# ProDoc_P1_2025-11-01.net
KiCad netlist of a schematic drawn in EasyEDA Pro
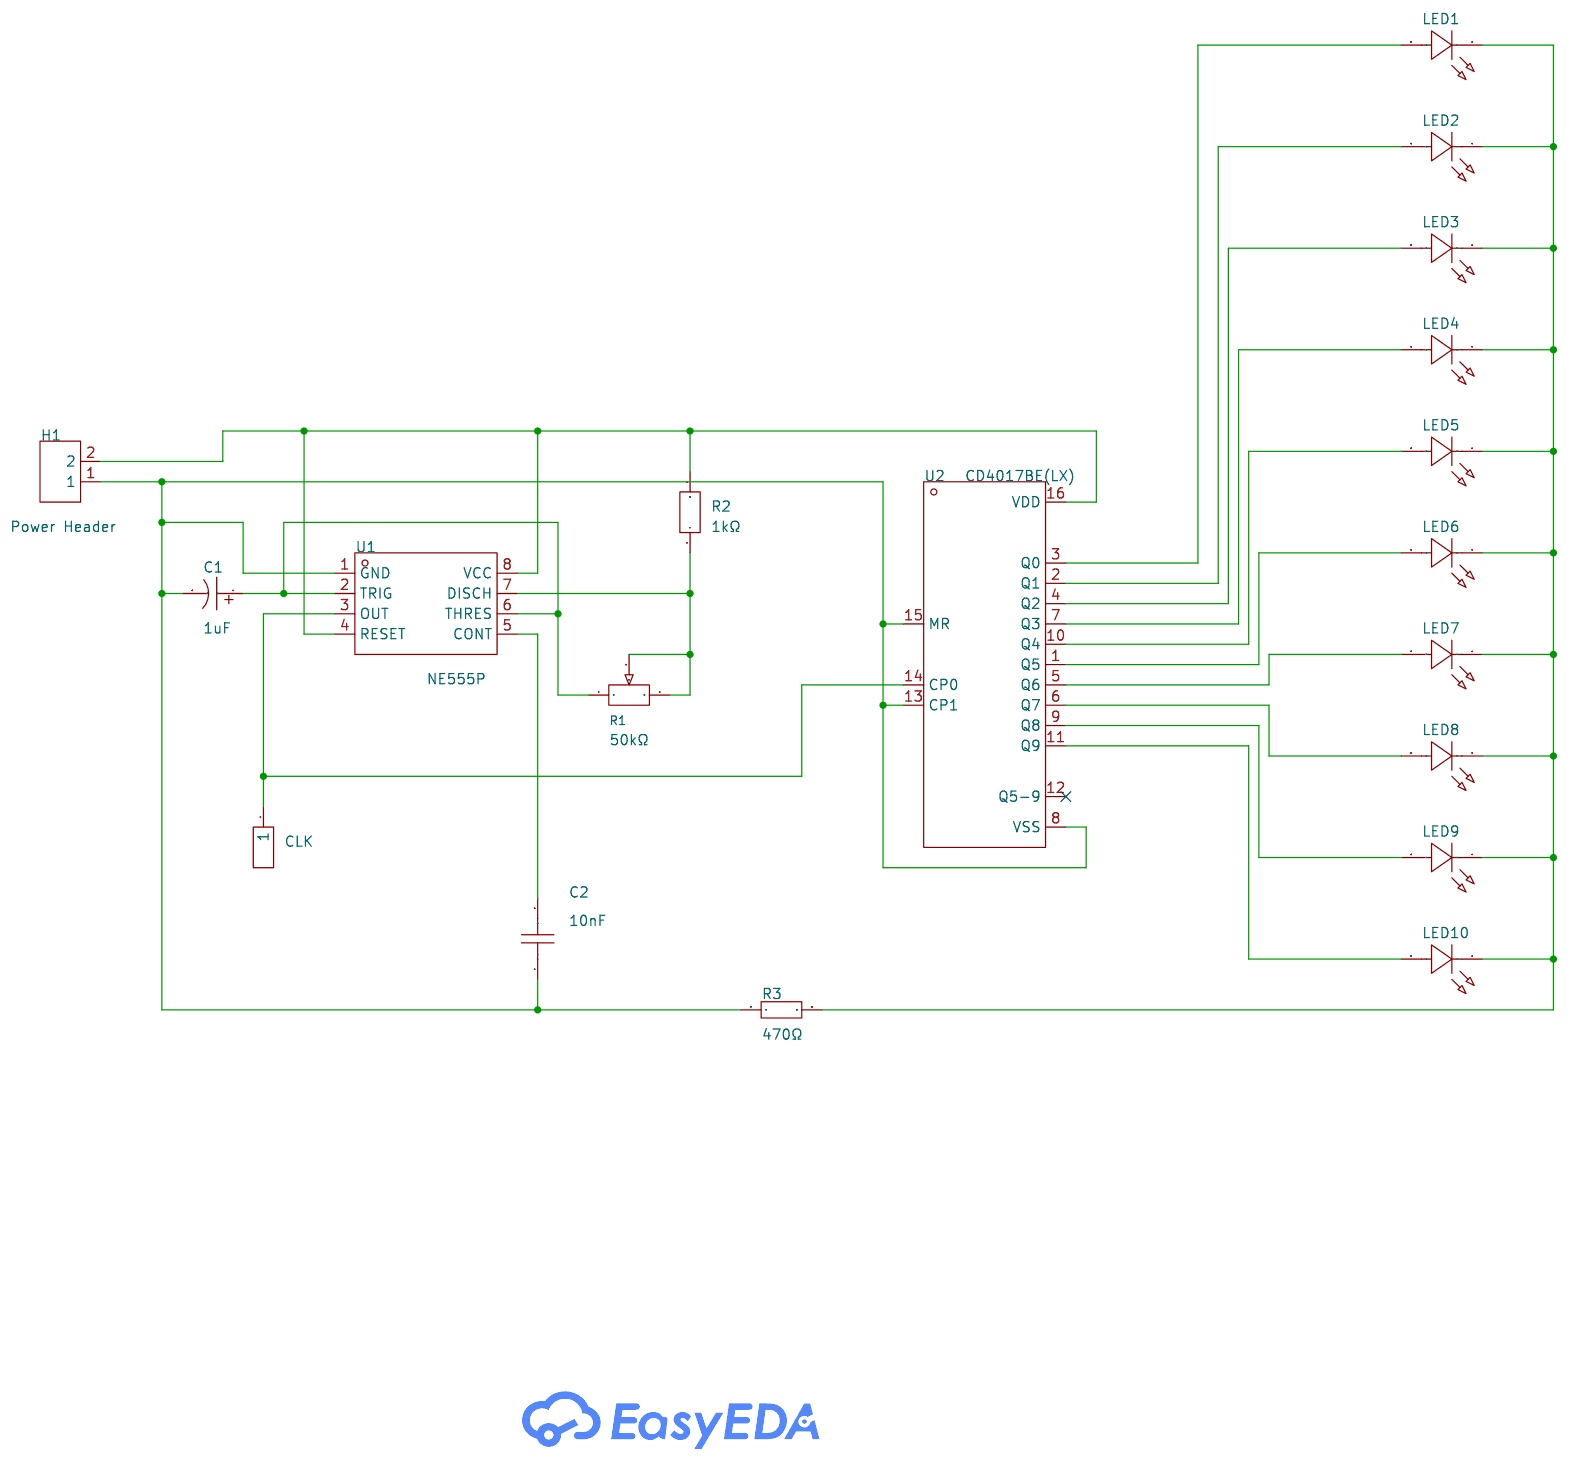
[diagram p0: schematic sheet]

(export (version "E")
  (design (tool "Eeschema 10.0.6"))
  (components
    (comp (ref "C1")
      (value "1uF")
      (footprint "easyedapro:CAP-TH_BD5.0-P2.00-D0.8-FD")
      (fields (field (name "Manufacturer Part") "KF010M050C110A") (field (name "Manufacturer") "CapXon(丰宾)"))
      (libsource (lib "easyedapro") (part "KF010M050C110A"))
    )
    (comp (ref "C2")
      (value "10nF")
      (footprint "easyedapro:CAP-TH_L8.0-W4.0-P5.00-D1.2")
      (fields (field (name "Manufacturer Part") "N09F1B103MN0B0S0N0") (field (name "Manufacturer") "STE(松田)"))
      (libsource (lib "easyedapro") (part "N09F1B103MN0B0S0N0"))
    )
    (comp (ref "CLK")
      (value "2.54-1*1P针")
      (footprint "easyedapro:HDR-TH_1P-P2.54-V-M")
      (fields (field (name "Manufacturer") "BOOMELE(博穆精密)"))
      (libsource (lib "easyedapro") (part "Header-Male-2.54_1x1"))
    )
    (comp (ref "H1")
      (value "Power Header")
      (footprint "easyedapro:HDR-TH_2P-P2.54-V-M")
      (fields (field (name "Manufacturer") "XFCN(兴飞)"))
      (libsource (lib "easyedapro") (part "PZ254V-11-02P"))
    )
    (comp (ref "LED1")
      (value "XL-502UWC")
      (footprint "easyedapro:LED-TH_BD5.9-P2.54-RD_WHITE")
      (fields (field (name "Manufacturer") "XINGLIGHT(成兴光)"))
      (libsource (lib "easyedapro") (part "XL-502UWC"))
    )
    (comp (ref "LED2")
      (value "XL-502UWC")
      (footprint "easyedapro:LED-TH_BD5.9-P2.54-RD_WHITE")
      (fields (field (name "Manufacturer") "XINGLIGHT(成兴光)"))
      (libsource (lib "easyedapro") (part "XL-502UWC"))
    )
    (comp (ref "LED3")
      (value "XL-502UWC")
      (footprint "easyedapro:LED-TH_BD5.9-P2.54-RD_WHITE")
      (fields (field (name "Manufacturer") "XINGLIGHT(成兴光)"))
      (libsource (lib "easyedapro") (part "XL-502UWC"))
    )
    (comp (ref "LED4")
      (value "XL-502UWC")
      (footprint "easyedapro:LED-TH_BD5.9-P2.54-RD_WHITE")
      (fields (field (name "Manufacturer") "XINGLIGHT(成兴光)"))
      (libsource (lib "easyedapro") (part "XL-502UWC"))
    )
    (comp (ref "LED5")
      (value "XL-502UWC")
      (footprint "easyedapro:LED-TH_BD5.9-P2.54-RD_WHITE")
      (fields (field (name "Manufacturer") "XINGLIGHT(成兴光)"))
      (libsource (lib "easyedapro") (part "XL-502UWC"))
    )
    (comp (ref "LED6")
      (value "XL-502UWC")
      (footprint "easyedapro:LED-TH_BD5.9-P2.54-RD_WHITE")
      (fields (field (name "Manufacturer") "XINGLIGHT(成兴光)"))
      (libsource (lib "easyedapro") (part "XL-502UWC"))
    )
    (comp (ref "LED7")
      (value "XL-502UWC")
      (footprint "easyedapro:LED-TH_BD5.9-P2.54-RD_WHITE")
      (fields (field (name "Manufacturer") "XINGLIGHT(成兴光)"))
      (libsource (lib "easyedapro") (part "XL-502UWC"))
    )
    (comp (ref "LED8")
      (value "XL-502UWC")
      (footprint "easyedapro:LED-TH_BD5.9-P2.54-RD_WHITE")
      (fields (field (name "Manufacturer") "XINGLIGHT(成兴光)"))
      (libsource (lib "easyedapro") (part "XL-502UWC"))
    )
    (comp (ref "LED9")
      (value "XL-502UWC")
      (footprint "easyedapro:LED-TH_BD5.9-P2.54-RD_WHITE")
      (fields (field (name "Manufacturer") "XINGLIGHT(成兴光)"))
      (libsource (lib "easyedapro") (part "XL-502UWC"))
    )
    (comp (ref "LED10")
      (value "XL-502UWC")
      (footprint "easyedapro:LED-TH_BD5.9-P2.54-RD_WHITE")
      (fields (field (name "Manufacturer") "XINGLIGHT(成兴光)"))
      (libsource (lib "easyedapro") (part "XL-502UWC"))
    )
    (comp (ref "R1")
      (value "50kΩ")
      (footprint "easyedapro:RES-ADJ-TH_3P-L9.5-W4.85-P2.50-BL-L")
      (fields (field (name "Manufacturer Part") "3296X-1-503") (field (name "Manufacturer") "BOCHEN(博晨)"))
      (libsource (lib "easyedapro") (part "3296X-1-503_C118912"))
    )
    (comp (ref "R2")
      (value "1kΩ")
      (footprint "easyedapro:RES-TH_BD2.3-L6.5-P10.50-D0.5")
      (fields (field (name "Manufacturer Part") "MF1/4W-1KΩ±1%T52") (field (name "Manufacturer") "华星机电"))
      (libsource (lib "easyedapro") (part "MF1/4W-1KΩ±1%T52"))
    )
    (comp (ref "R3")
      (value "470Ω")
      (footprint "easyedapro:RES-TH_BD2.2-L6.5-P10.50-D0.6")
      (fields
        (field (name "Manufacturer Part") "MFR0W4F4700A50")
        (field (name "Manufacturer") "UNI-ROYAL(厚声)")
      )
      (libsource (lib "easyedapro") (part "MFR0W4F4700A50"))
    )
    (comp (ref "U1")
      (value "NE555P")
      (footprint "easyedapro:DIP-8_L9.8-W6.6-P2.54-LS7.6-BL")
      (fields (field (name "Manufacturer") "TI(德州仪器)"))
      (libsource (lib "easyedapro") (part "NE555P"))
    )
    (comp (ref "U2")
      (value "CD4017BE(LX)")
      (footprint "easyedapro:PDIP-16_L19.3-W6.4-P2.54-LS7.94-BL")
      (fields (field (name "Manufacturer") "LX(灵星芯微)"))
      (libsource (lib "easyedapro") (part "CD4017BE(LX)"))
    )
  )
  (nets
    (net (code "1") (name "Net-(LED1-A)") (class "Default")
      (node (ref "LED1") (pin "2") (pinfunction "A_2") (pintype "unspecified"))
      (node (ref "U2") (pin "3") (pinfunction "Q0_3") (pintype "unspecified"))
    )
    (net (code "2") (name "Net-(LED1-K)") (class "Default")
      (node (ref "LED1") (pin "1") (pinfunction "K_1") (pintype "unspecified"))
      (node (ref "LED10") (pin "1") (pinfunction "K_1") (pintype "unspecified"))
      (node (ref "LED2") (pin "1") (pinfunction "K_1") (pintype "unspecified"))
      (node (ref "LED3") (pin "1") (pinfunction "K_1") (pintype "unspecified"))
      (node (ref "LED4") (pin "1") (pinfunction "K_1") (pintype "unspecified"))
      (node (ref "LED5") (pin "1") (pinfunction "K_1") (pintype "unspecified"))
      (node (ref "LED6") (pin "1") (pinfunction "K_1") (pintype "unspecified"))
      (node (ref "LED7") (pin "1") (pinfunction "K_1") (pintype "unspecified"))
      (node (ref "LED8") (pin "1") (pinfunction "K_1") (pintype "unspecified"))
      (node (ref "LED9") (pin "1") (pinfunction "K_1") (pintype "unspecified"))
      (node (ref "R3") (pin "2") (pinfunction "2_2") (pintype "input"))
    )
    (net (code "3") (name "Net-(LED2-A)") (class "Default")
      (node (ref "LED2") (pin "2") (pinfunction "A_2") (pintype "unspecified"))
      (node (ref "U2") (pin "2") (pinfunction "Q1_2") (pintype "unspecified"))
    )
    (net (code "4") (name "Net-(LED3-A)") (class "Default")
      (node (ref "LED3") (pin "2") (pinfunction "A_2") (pintype "unspecified"))
      (node (ref "U2") (pin "4") (pinfunction "Q2_4") (pintype "unspecified"))
    )
    (net (code "5") (name "Net-(LED4-A)") (class "Default")
      (node (ref "LED4") (pin "2") (pinfunction "A_2") (pintype "unspecified"))
      (node (ref "U2") (pin "7") (pinfunction "Q3_7") (pintype "unspecified"))
    )
    (net (code "6") (name "Net-(LED5-A)") (class "Default")
      (node (ref "LED5") (pin "2") (pinfunction "A_2") (pintype "unspecified"))
      (node (ref "U2") (pin "10") (pinfunction "Q4_10") (pintype "unspecified"))
    )
    (net (code "7") (name "Net-(LED6-A)") (class "Default")
      (node (ref "LED6") (pin "2") (pinfunction "A_2") (pintype "unspecified"))
      (node (ref "U2") (pin "1") (pinfunction "Q5_1") (pintype "unspecified"))
    )
    (net (code "8") (name "Net-(LED7-A)") (class "Default")
      (node (ref "LED7") (pin "2") (pinfunction "A_2") (pintype "unspecified"))
      (node (ref "U2") (pin "5") (pinfunction "Q6_5") (pintype "unspecified"))
    )
    (net (code "9") (name "Net-(LED8-A)") (class "Default")
      (node (ref "LED8") (pin "2") (pinfunction "A_2") (pintype "unspecified"))
      (node (ref "U2") (pin "6") (pinfunction "Q7_6") (pintype "unspecified"))
    )
    (net (code "10") (name "Net-(LED9-A)") (class "Default")
      (node (ref "LED9") (pin "2") (pinfunction "A_2") (pintype "unspecified"))
      (node (ref "U2") (pin "9") (pinfunction "Q8_9") (pintype "unspecified"))
    )
    (net (code "11") (name "Net-(LED10-A)") (class "Default")
      (node (ref "LED10") (pin "2") (pinfunction "A_2") (pintype "unspecified"))
      (node (ref "U2") (pin "11") (pinfunction "Q9_11") (pintype "unspecified"))
    )
    (net (code "12") (name "Net-(U1-CONT)") (class "Default")
      (node (ref "C2") (pin "2") (pinfunction "2_2") (pintype "unspecified"))
      (node (ref "U1") (pin "5") (pinfunction "CONT_5") (pintype "input"))
    )
    (net (code "13") (name "Net-(U1-DISCH)") (class "Default")
      (node (ref "R1") (pin "2") (pinfunction "2_2") (pintype "input"))
      (node (ref "R1") (pin "3") (pinfunction "3_3") (pintype "input"))
      (node (ref "R2") (pin "1") (pinfunction "1_1") (pintype "unspecified"))
      (node (ref "U1") (pin "7") (pinfunction "DISCH_7") (pintype "input"))
    )
    (net (code "14") (name "Net-(U1-GND)") (class "Default")
      (node (ref "C1") (pin "2") (pinfunction "2_2") (pintype "input"))
      (node (ref "C2") (pin "1") (pinfunction "1_1") (pintype "unspecified"))
      (node (ref "H1") (pin "1") (pinfunction "1_1") (pintype "unspecified"))
      (node (ref "R3") (pin "1") (pinfunction "1_1") (pintype "input"))
      (node (ref "U1") (pin "1") (pinfunction "GND_1") (pintype "input"))
      (node (ref "U2") (pin "13") (pinfunction "CP1_13") (pintype "unspecified"))
      (node (ref "U2") (pin "15") (pinfunction "MR_15") (pintype "unspecified"))
      (node (ref "U2") (pin "8") (pinfunction "VSS_8") (pintype "unspecified"))
    )
    (net (code "15") (name "Net-(U1-OUT)") (class "Default")
      (node (ref "CLK") (pin "1") (pinfunction "1_1") (pintype "input"))
      (node (ref "U1") (pin "3") (pinfunction "OUT_3") (pintype "input"))
      (node (ref "U2") (pin "14") (pinfunction "CP0_14") (pintype "unspecified"))
    )
    (net (code "16") (name "Net-(U1-RESET)") (class "Default")
      (node (ref "H1") (pin "2") (pinfunction "2_2") (pintype "unspecified"))
      (node (ref "R2") (pin "2") (pinfunction "2_2") (pintype "unspecified"))
      (node (ref "U1") (pin "4") (pinfunction "RESET_4") (pintype "input"))
      (node (ref "U1") (pin "8") (pinfunction "VCC_8") (pintype "input"))
      (node (ref "U2") (pin "16") (pinfunction "VDD_16") (pintype "unspecified"))
    )
    (net (code "17") (name "Net-(U1-THRES)") (class "Default")
      (node (ref "C1") (pin "1") (pinfunction "1_1") (pintype "input"))
      (node (ref "R1") (pin "1") (pinfunction "1_1") (pintype "input"))
      (node (ref "U1") (pin "2") (pinfunction "TRIG_2") (pintype "input"))
      (node (ref "U1") (pin "6") (pinfunction "THRES_6") (pintype "input"))
    )
    (net (code "18") (name "unconnected-(U2-Q5-9-Pad12)") (class "Default")
      (node (ref "U2") (pin "12") (pinfunction "Q5-9_12") (pintype "unspecified+no_connect"))
    )
  )
)
